# ID4.net
KiCad netlist of a schematic drawn in Altium Designer
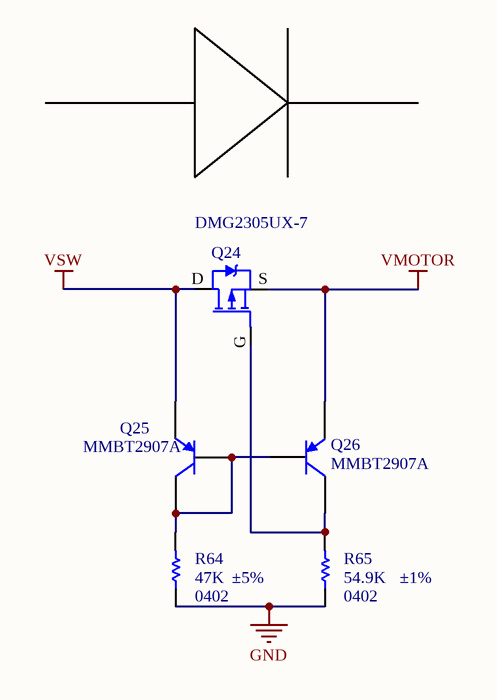
[diagram p0: ID4.SchDoc]

(export (version "E")
  (design (tool "Eeschema 10.0.6"))
  (components
    (comp (ref "Q24")
      (value "DMG2305UX")
      (footprint "DMG2305UX-7")
      (description "MOSFET P-CH 20V 4.2A SOT23")
      (fields
        (field (name "MANUFACTURER") "Diodes Incorporated")
        (field (name "MANUFACTURER PART NUMBER") "DMG2305UX-7")
        (field (name "CREATOR") "osman")
      )
      (libsource (lib "OLogic-Trans-Drivers") (part "DMG2305UX"))
    )
    (comp (ref "Q25")
      (value "MMBT2907A")
      (footprint "SOT23")
      (description "PNP General Purpose Amplifier")
      (fields (field (name "MANUFACTURER") "Fairchild Semiconductor"))
      (libsource (lib "OLogic-Trans-Drivers") (part "MMBT2907A"))
    )
    (comp (ref "Q26")
      (value "MMBT2907A")
      (footprint "SOT23")
      (description "PNP General Purpose Amplifier")
      (fields (field (name "MANUFACTURER") "Fairchild Semiconductor"))
      (libsource (lib "OLogic-Trans-Drivers") (part "MMBT2907A"))
    )
    (comp (ref "R64")
      (value "47K")
      (footprint "RESC0402(1005)_N")
      (description "47K 0402")
      (fields
        (field (name "MANUFACTURER") "Panasonic Electronic Components")
        (field (name "MANUFACTURER PART NUMBER") "ERJ-2GEJ473X")
        (field (name "TOLERANCE") "±5%")
        (field (name "SUPPLIER DEVICE PACKAGE") "0402")
      )
      (libsource (lib "OLogic-Passive") (part "RES 47K OHM 5% 1/10W 0402"))
    )
    (comp (ref "R65")
      (value "54.9K")
      (footprint "RESC0402(1005)_N")
      (description "54.9K 1% 0402")
      (fields
        (field (name "MANUFACTURER") "Panasonic Electronic Components")
        (field (name "MANUFACTURER PART NUMBER") "ERJ-2RKF5492X")
        (field (name "TOLERANCE") "±1%")
        (field (name "SUPPLIER DEVICE PACKAGE") "0402")
      )
      (libsource (lib "OLogic-Passive") (part "RES 54.9K OHM 1% 1/10W 0402"))
    )
  )
  (nets
    (net (code "1") (name "GND") (class "Default")
      (node (ref "R64") (pin "1") (pinfunction "1_1") (pintype "passive"))
      (node (ref "R65") (pin "1") (pinfunction "1_1") (pintype "passive"))
    )
    (net (code "2") (name "Net-(Q25-B)") (class "Default")
      (node (ref "Q25") (pin "1") (pinfunction "B_1") (pintype "passive"))
      (node (ref "Q25") (pin "3") (pinfunction "C_3") (pintype "passive"))
      (node (ref "Q26") (pin "1") (pinfunction "B_1") (pintype "passive"))
      (node (ref "R64") (pin "2") (pinfunction "2_2") (pintype "passive"))
    )
    (net (code "3") (name "Net-(Q26-C)") (class "Default")
      (node (ref "Q24") (pin "G") (pinfunction "G_G") (pintype "passive"))
      (node (ref "Q26") (pin "3") (pinfunction "C_3") (pintype "passive"))
      (node (ref "R65") (pin "2") (pinfunction "2_2") (pintype "passive"))
    )
    (net (code "4") (name "VMOTOR") (class "Default")
      (node (ref "Q24") (pin "S") (pinfunction "S_S") (pintype "passive"))
      (node (ref "Q26") (pin "2") (pinfunction "E_2") (pintype "passive"))
    )
    (net (code "5") (name "VSW") (class "Default")
      (node (ref "Q24") (pin "D") (pinfunction "D_D") (pintype "passive"))
      (node (ref "Q25") (pin "2") (pinfunction "E_2") (pintype "passive"))
    )
  )
)
